# A2_relay_v40.net
KiCad netlist of a schematic drawn in Altium Designer
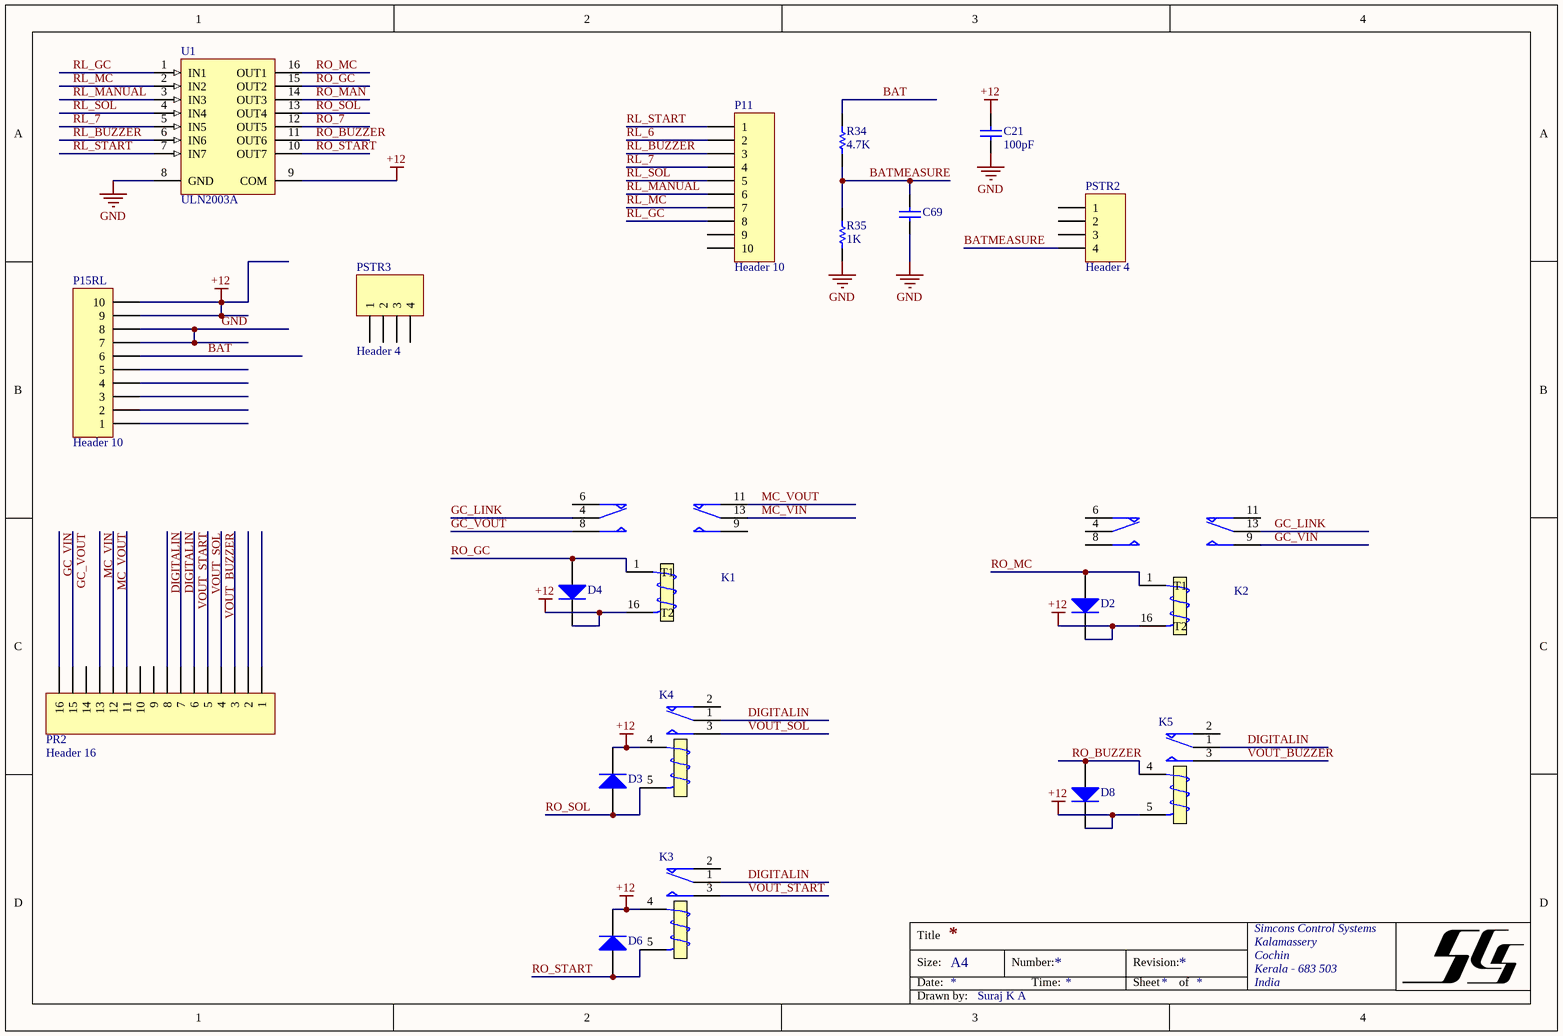
[diagram p0: A2_relay_v40.SchDoc]

(export (version "E")
  (design (tool "Eeschema 10.0.6"))
  (components
    (comp (ref "C21")
      (value "100pF")
      (footprint "CAP DISC .2")
      (description "Capacitor")
      (fields (field (name "Comment") "1uF 1206") (field (name "PUBLISHER") "Altium Limited"))
      (libsource (lib "Miscellaneous Devices") (part "Cap"))
    )
    (comp (ref "C69")
      (value "1uF 1206")
      (footprint "CAP DISC .2")
      (description "Capacitor")
      (fields (field (name "PUBLISHER") "Altium Limited"))
      (libsource (lib "Miscellaneous Devices") (part "Cap"))
    )
    (comp (ref "D2")
      (value "1N4007")
      (footprint "DIODE1A")
      (description "Small Signal Fast Switching Diode")
      (fields (field (name "PUBLISHER") "Altium Limited"))
      (libsource (lib "Miscellaneous Devices") (part "Diode 1N5408"))
    )
    (comp (ref "D3")
      (value "1N4007")
      (footprint "DIODE1A")
      (description "Small Signal Fast Switching Diode")
      (fields (field (name "PUBLISHER") "Altium Limited"))
      (libsource (lib "Miscellaneous Devices") (part "Diode 1N5408"))
    )
    (comp (ref "D4")
      (value "1N4007")
      (footprint "DIODE1A")
      (description "Small Signal Fast Switching Diode")
      (fields (field (name "PUBLISHER") "Altium Limited"))
      (libsource (lib "Miscellaneous Devices") (part "Diode 1N5408"))
    )
    (comp (ref "D6")
      (value "1N4007")
      (footprint "DIODE1A")
      (description "Small Signal Fast Switching Diode")
      (fields (field (name "PUBLISHER") "Altium Limited"))
      (libsource (lib "Miscellaneous Devices") (part "Diode 1N5408"))
    )
    (comp (ref "D8")
      (value "1N4007")
      (footprint "DIODE1A")
      (description "Small Signal Fast Switching Diode")
      (fields (field (name "PUBLISHER") "Altium Limited"))
      (libsource (lib "Miscellaneous Devices") (part "Diode 1N5408"))
    )
    (comp (ref "K1")
      (value "46-12-2CE")
      (footprint "RELAYDPDT")
      (description "DPDT RELAY")
      (libsource (lib "PCB_Project1") (part "RELAYDPDT"))
    )
    (comp (ref "K2")
      (value "46-12-2CE")
      (footprint "RELAYDPDT")
      (description "DPDT RELAY")
      (libsource (lib "PCB_Project1") (part "RELAYDPDT"))
    )
    (comp (ref "K3")
      (value "61-06-1CE")
      (footprint "RELAY")
      (description "SPDT Relay")
      (fields (field (name "PUBLISHER") "Altium Limited"))
      (libsource (lib "Miscellaneous Devices") (part "Relay"))
    )
    (comp (ref "K4")
      (value "61-06-1CE")
      (footprint "RELAY")
      (description "SPDT Relay")
      (fields (field (name "PUBLISHER") "Altium Limited"))
      (libsource (lib "Miscellaneous Devices") (part "Relay"))
    )
    (comp (ref "K5")
      (value "61-06-1CE")
      (footprint "RELAY")
      (description "SPDT Relay")
      (fields (field (name "PUBLISHER") "Altium Limited"))
      (libsource (lib "Miscellaneous Devices") (part "Relay"))
    )
    (comp (ref "P11")
      (value "Header 10")
      (footprint "HDR1X10_BURGE_M2")
      (description "Header, 10-Pin")
      (fields (field (name "PUBLISHER") "Altium Limited"))
      (libsource (lib "") (part "Header 10_1"))
    )
    (comp (ref "P15RL")
      (value "Header 10")
      (footprint "HDR1X10_BURGE_M")
      (description "Header, 10-Pin")
      (fields (field (name "PUBLISHER") "Altium Limited"))
      (libsource (lib "Miscellaneous Connectors") (part "Header 10"))
    )
    (comp (ref "PR2")
      (value "Header 16")
      (footprint "HDR1X16_BURGE_M")
      (description "Header, 16-Pin")
      (fields (field (name "PUBLISHER") "Altium Limited"))
      (libsource (lib "Miscellaneous Connectors") (part "Header 16"))
    )
    (comp (ref "PSTR2")
      (value "Header 4")
      (footprint "HDR1X4_BURGE_M")
      (description "Header, 4-Pin")
      (fields (field (name "PUBLISHER") "Altium Limited"))
      (libsource (lib "Miscellaneous Connectors") (part "Header 4"))
    )
    (comp (ref "PSTR3")
      (value "Header 4")
      (footprint "HDR1X4_BURGE_M")
      (description "Header, 4-Pin")
      (fields (field (name "PUBLISHER") "Altium Limited"))
      (libsource (lib "") (part "Header 4_1"))
    )
    (comp (ref "R34")
      (value "4.7K")
      (footprint "AXIAL-0.4")
      (description "Resistor")
      (fields (field (name "Comment") "47K 1206") (field (name "PUBLISHER") "Altium Limited"))
      (libsource (lib "Miscellaneous Devices") (part "Res1"))
    )
    (comp (ref "R35")
      (value "1K")
      (footprint "AXIAL-0.4")
      (description "Resistor")
      (fields (field (name "Comment") "4.7K 1206") (field (name "PUBLISHER") "Altium Limited"))
      (libsource (lib "Miscellaneous Devices") (part "Res1"))
    )
    (comp (ref "U1")
      (value "ULN2003A")
      (footprint "DIP-16")
      (description "Seven Darlington Array")
      (fields (field (name "PUBLISHER") "Altium Limited"))
      (libsource (lib "ST Interface Darlington Driver") (part "ULN2003A"))
    )
  )
  (nets
    (net (code "1") (name "+12") (class "Default")
      (node (ref "C21") (pin "2") (pinfunction "2_2") (pintype "passive"))
      (node (ref "D2") (pin "2") (pinfunction "K_2") (pintype "passive"))
      (node (ref "D3") (pin "2") (pinfunction "K_2") (pintype "passive"))
      (node (ref "D4") (pin "2") (pinfunction "K_2") (pintype "passive"))
      (node (ref "D6") (pin "2") (pinfunction "K_2") (pintype "passive"))
      (node (ref "D8") (pin "2") (pinfunction "K_2") (pintype "passive"))
      (node (ref "K1") (pin "16") (pinfunction "T2_16") (pintype "passive"))
      (node (ref "K2") (pin "16") (pinfunction "T2_16") (pintype "passive"))
      (node (ref "K3") (pin "4") (pinfunction "T1_4") (pintype "passive"))
      (node (ref "K4") (pin "4") (pinfunction "T1_4") (pintype "passive"))
      (node (ref "K5") (pin "5") (pinfunction "T2_5") (pintype "passive"))
      (node (ref "P15RL") (pin "10") (pinfunction "10_10") (pintype "passive"))
      (node (ref "P15RL") (pin "9") (pinfunction "9_9") (pintype "passive"))
      (node (ref "U1") (pin "9") (pinfunction "COM_9") (pintype "passive"))
    )
    (net (code "2") (name "/BAT") (class "Default")
      (node (ref "P15RL") (pin "6") (pinfunction "6_6") (pintype "passive"))
      (node (ref "R34") (pin "2") (pinfunction "2_2") (pintype "passive"))
    )
    (net (code "3") (name "/BATMEASURE") (class "Default")
      (node (ref "C69") (pin "2") (pinfunction "2_2") (pintype "passive"))
      (node (ref "PSTR2") (pin "4") (pinfunction "4_4") (pintype "passive"))
      (node (ref "R34") (pin "1") (pinfunction "1_1") (pintype "passive"))
      (node (ref "R35") (pin "2") (pinfunction "2_2") (pintype "passive"))
    )
    (net (code "4") (name "/DIGITALIN") (class "Default")
      (node (ref "K3") (pin "1") (pinfunction "COM_1") (pintype "passive"))
      (node (ref "K4") (pin "1") (pinfunction "COM_1") (pintype "passive"))
      (node (ref "K5") (pin "1") (pinfunction "COM_1") (pintype "passive"))
      (node (ref "PR2") (pin "7") (pinfunction "7_7") (pintype "passive"))
      (node (ref "PR2") (pin "8") (pinfunction "8_8") (pintype "passive"))
    )
    (net (code "5") (name "/GC_LINK") (class "Default")
      (node (ref "K1") (pin "4") (pinfunction "COM_4") (pintype "passive"))
      (node (ref "K2") (pin "13") (pinfunction "COM_13") (pintype "passive"))
    )
    (net (code "6") (name "/GC_VIN") (class "Default")
      (node (ref "K2") (pin "9") (pinfunction "NO_9") (pintype "passive"))
      (node (ref "PR2") (pin "16") (pinfunction "16_16") (pintype "passive"))
    )
    (net (code "7") (name "/GC_VOUT") (class "Default")
      (node (ref "K1") (pin "8") (pinfunction "NO_8") (pintype "passive"))
      (node (ref "PR2") (pin "15") (pinfunction "15_15") (pintype "passive"))
    )
    (net (code "8") (name "/MC_VIN") (class "Default")
      (node (ref "K1") (pin "13") (pinfunction "COM_13") (pintype "passive"))
      (node (ref "PR2") (pin "13") (pinfunction "13_13") (pintype "passive"))
    )
    (net (code "9") (name "/MC_VOUT") (class "Default")
      (node (ref "K1") (pin "11") (pinfunction "NC_11") (pintype "passive"))
      (node (ref "PR2") (pin "12") (pinfunction "12_12") (pintype "passive"))
    )
    (net (code "10") (name "/RL_6") (class "Default")
      (node (ref "P11") (pin "2") (pinfunction "2_2") (pintype "passive"))
    )
    (net (code "11") (name "/RL_7") (class "Default")
      (node (ref "P11") (pin "4") (pinfunction "4_4") (pintype "passive"))
      (node (ref "U1") (pin "5") (pinfunction "IN5_5") (pintype "input"))
    )
    (net (code "12") (name "/RL_BUZZER") (class "Default")
      (node (ref "P11") (pin "3") (pinfunction "3_3") (pintype "passive"))
      (node (ref "U1") (pin "6") (pinfunction "IN6_6") (pintype "input"))
    )
    (net (code "13") (name "/RL_GC") (class "Default")
      (node (ref "P11") (pin "8") (pinfunction "8_8") (pintype "passive"))
      (node (ref "U1") (pin "1") (pinfunction "IN1_1") (pintype "input"))
    )
    (net (code "14") (name "/RL_MANUAL") (class "Default")
      (node (ref "P11") (pin "6") (pinfunction "6_6") (pintype "passive"))
      (node (ref "U1") (pin "3") (pinfunction "IN3_3") (pintype "input"))
    )
    (net (code "15") (name "/RL_MC") (class "Default")
      (node (ref "P11") (pin "7") (pinfunction "7_7") (pintype "passive"))
      (node (ref "U1") (pin "2") (pinfunction "IN2_2") (pintype "input"))
    )
    (net (code "16") (name "/RL_SOL") (class "Default")
      (node (ref "P11") (pin "5") (pinfunction "5_5") (pintype "passive"))
      (node (ref "U1") (pin "4") (pinfunction "IN4_4") (pintype "input"))
    )
    (net (code "17") (name "/RL_START") (class "Default")
      (node (ref "P11") (pin "1") (pinfunction "1_1") (pintype "passive"))
      (node (ref "U1") (pin "7") (pinfunction "IN7_7") (pintype "input"))
    )
    (net (code "18") (name "/RO_7") (class "Default")
      (node (ref "U1") (pin "12") (pinfunction "OUT5_12") (pintype "open_collector"))
    )
    (net (code "19") (name "/RO_BUZZER") (class "Default")
      (node (ref "D8") (pin "1") (pinfunction "A_1") (pintype "passive"))
      (node (ref "K5") (pin "4") (pinfunction "T1_4") (pintype "passive"))
      (node (ref "U1") (pin "11") (pinfunction "OUT6_11") (pintype "open_collector"))
    )
    (net (code "20") (name "/RO_GC") (class "Default")
      (node (ref "D4") (pin "1") (pinfunction "A_1") (pintype "passive"))
      (node (ref "K1") (pin "1") (pinfunction "T1_1") (pintype "passive"))
      (node (ref "U1") (pin "15") (pinfunction "OUT2_15") (pintype "open_collector"))
    )
    (net (code "21") (name "/RO_MAN") (class "Default")
      (node (ref "U1") (pin "14") (pinfunction "OUT3_14") (pintype "open_collector"))
    )
    (net (code "22") (name "/RO_MC") (class "Default")
      (node (ref "D2") (pin "1") (pinfunction "A_1") (pintype "passive"))
      (node (ref "K2") (pin "1") (pinfunction "T1_1") (pintype "passive"))
      (node (ref "U1") (pin "16") (pinfunction "OUT1_16") (pintype "open_collector"))
    )
    (net (code "23") (name "/RO_SOL") (class "Default")
      (node (ref "D3") (pin "1") (pinfunction "A_1") (pintype "passive"))
      (node (ref "K4") (pin "5") (pinfunction "T2_5") (pintype "passive"))
      (node (ref "U1") (pin "13") (pinfunction "OUT4_13") (pintype "open_collector"))
    )
    (net (code "24") (name "/RO_START") (class "Default")
      (node (ref "D6") (pin "1") (pinfunction "A_1") (pintype "passive"))
      (node (ref "K3") (pin "5") (pinfunction "T2_5") (pintype "passive"))
      (node (ref "U1") (pin "10") (pinfunction "OUT7_10") (pintype "open_collector"))
    )
    (net (code "25") (name "/VOUT_BUZZER") (class "Default")
      (node (ref "K5") (pin "3") (pinfunction "NO_3") (pintype "passive"))
      (node (ref "PR2") (pin "4") (pinfunction "4_4") (pintype "passive"))
    )
    (net (code "26") (name "/VOUT_SOL") (class "Default")
      (node (ref "K4") (pin "3") (pinfunction "NO_3") (pintype "passive"))
      (node (ref "PR2") (pin "5") (pinfunction "5_5") (pintype "passive"))
    )
    (net (code "27") (name "/VOUT_START") (class "Default")
      (node (ref "K3") (pin "3") (pinfunction "NO_3") (pintype "passive"))
      (node (ref "PR2") (pin "6") (pinfunction "6_6") (pintype "passive"))
    )
    (net (code "28") (name "GND") (class "Default")
      (node (ref "C21") (pin "1") (pinfunction "1_1") (pintype "passive"))
      (node (ref "C69") (pin "1") (pinfunction "1_1") (pintype "passive"))
      (node (ref "P15RL") (pin "7") (pinfunction "7_7") (pintype "passive"))
      (node (ref "P15RL") (pin "8") (pinfunction "8_8") (pintype "passive"))
      (node (ref "R35") (pin "1") (pinfunction "1_1") (pintype "passive"))
      (node (ref "U1") (pin "8") (pinfunction "GND_8") (pintype "power_in"))
    )
    (net (code "29") (name "unconnected-(K1-NC-Pad6)") (class "Default")
      (node (ref "K1") (pin "6") (pinfunction "NC_6") (pintype "passive"))
    )
    (net (code "30") (name "unconnected-(K1-NO-Pad9)") (class "Default")
      (node (ref "K1") (pin "9") (pinfunction "NO_9") (pintype "passive"))
    )
    (net (code "31") (name "unconnected-(K2-COM-Pad4)") (class "Default")
      (node (ref "K2") (pin "4") (pinfunction "COM_4") (pintype "passive"))
    )
    (net (code "32") (name "unconnected-(K2-NC-Pad6)") (class "Default")
      (node (ref "K2") (pin "6") (pinfunction "NC_6") (pintype "passive"))
    )
    (net (code "33") (name "unconnected-(K2-NC-Pad11)") (class "Default")
      (node (ref "K2") (pin "11") (pinfunction "NC_11") (pintype "passive"))
    )
    (net (code "34") (name "unconnected-(K2-NO-Pad8)") (class "Default")
      (node (ref "K2") (pin "8") (pinfunction "NO_8") (pintype "passive"))
    )
    (net (code "35") (name "unconnected-(K3-NC-Pad2)") (class "Default")
      (node (ref "K3") (pin "2") (pinfunction "NC_2") (pintype "passive"))
    )
    (net (code "36") (name "unconnected-(K4-NC-Pad2)") (class "Default")
      (node (ref "K4") (pin "2") (pinfunction "NC_2") (pintype "passive"))
    )
    (net (code "37") (name "unconnected-(K5-NC-Pad2)") (class "Default")
      (node (ref "K5") (pin "2") (pinfunction "NC_2") (pintype "passive"))
    )
    (net (code "38") (name "unconnected-(P11-Pad9)") (class "Default")
      (node (ref "P11") (pin "9") (pinfunction "9_9") (pintype "passive"))
    )
    (net (code "39") (name "unconnected-(P11-Pad10)") (class "Default")
      (node (ref "P11") (pin "10") (pinfunction "10_10") (pintype "passive"))
    )
    (net (code "40") (name "unconnected-(P15RL-Pad1)") (class "Default")
      (node (ref "P15RL") (pin "1") (pinfunction "1_1") (pintype "passive"))
    )
    (net (code "41") (name "unconnected-(P15RL-Pad2)") (class "Default")
      (node (ref "P15RL") (pin "2") (pinfunction "2_2") (pintype "passive"))
    )
    (net (code "42") (name "unconnected-(P15RL-Pad3)") (class "Default")
      (node (ref "P15RL") (pin "3") (pinfunction "3_3") (pintype "passive"))
    )
    (net (code "43") (name "unconnected-(P15RL-Pad4)") (class "Default")
      (node (ref "P15RL") (pin "4") (pinfunction "4_4") (pintype "passive"))
    )
    (net (code "44") (name "unconnected-(P15RL-Pad5)") (class "Default")
      (node (ref "P15RL") (pin "5") (pinfunction "5_5") (pintype "passive"))
    )
    (net (code "45") (name "unconnected-(PR2-Pad1)") (class "Default")
      (node (ref "PR2") (pin "1") (pinfunction "1_1") (pintype "passive"))
    )
    (net (code "46") (name "unconnected-(PR2-Pad2)") (class "Default")
      (node (ref "PR2") (pin "2") (pinfunction "2_2") (pintype "passive"))
    )
    (net (code "47") (name "unconnected-(PR2-Pad3)") (class "Default")
      (node (ref "PR2") (pin "3") (pinfunction "3_3") (pintype "passive"))
    )
    (net (code "48") (name "unconnected-(PR2-Pad9)") (class "Default")
      (node (ref "PR2") (pin "9") (pinfunction "9_9") (pintype "passive"))
    )
    (net (code "49") (name "unconnected-(PR2-Pad10)") (class "Default")
      (node (ref "PR2") (pin "10") (pinfunction "10_10") (pintype "passive"))
    )
    (net (code "50") (name "unconnected-(PR2-Pad11)") (class "Default")
      (node (ref "PR2") (pin "11") (pinfunction "11_11") (pintype "passive"))
    )
    (net (code "51") (name "unconnected-(PR2-Pad14)") (class "Default")
      (node (ref "PR2") (pin "14") (pinfunction "14_14") (pintype "passive"))
    )
    (net (code "52") (name "unconnected-(PSTR2-Pad1)") (class "Default")
      (node (ref "PSTR2") (pin "1") (pinfunction "1_1") (pintype "passive"))
    )
    (net (code "53") (name "unconnected-(PSTR2-Pad2)") (class "Default")
      (node (ref "PSTR2") (pin "2") (pinfunction "2_2") (pintype "passive"))
    )
    (net (code "54") (name "unconnected-(PSTR2-Pad3)") (class "Default")
      (node (ref "PSTR2") (pin "3") (pinfunction "3_3") (pintype "passive"))
    )
    (net (code "55") (name "unconnected-(PSTR3-Pad1)") (class "Default")
      (node (ref "PSTR3") (pin "1") (pinfunction "1_1") (pintype "passive"))
    )
    (net (code "56") (name "unconnected-(PSTR3-Pad2)") (class "Default")
      (node (ref "PSTR3") (pin "2") (pinfunction "2_2") (pintype "passive"))
    )
    (net (code "57") (name "unconnected-(PSTR3-Pad3)") (class "Default")
      (node (ref "PSTR3") (pin "3") (pinfunction "3_3") (pintype "passive"))
    )
    (net (code "58") (name "unconnected-(PSTR3-Pad4)") (class "Default")
      (node (ref "PSTR3") (pin "4") (pinfunction "4_4") (pintype "passive"))
    )
  )
)
